# Main_v1.net
KiCad netlist of a schematic drawn in EAGLE
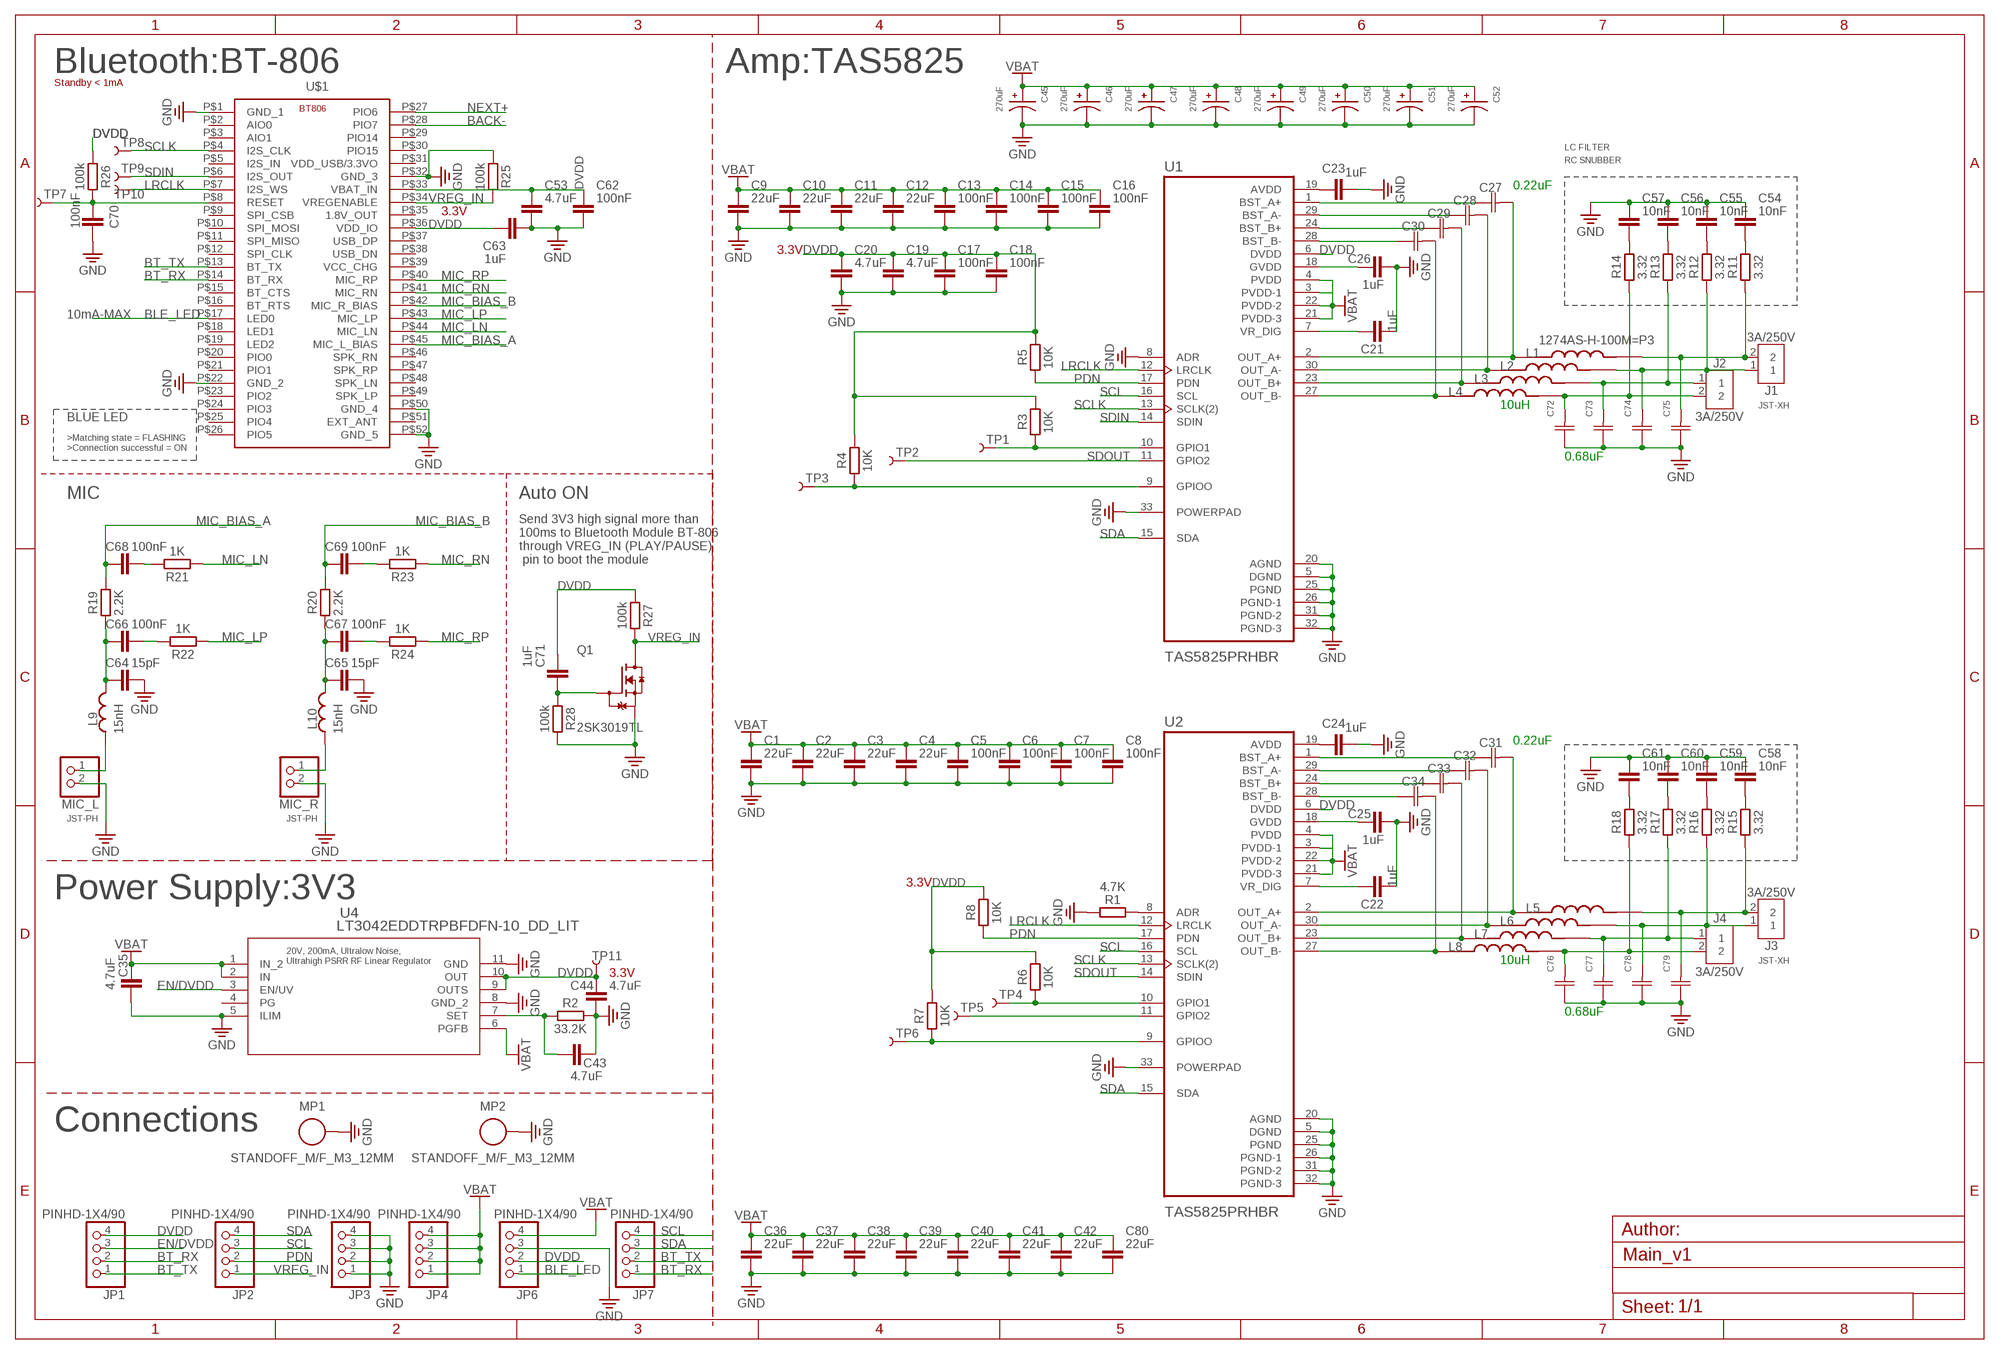
[diagram p0: schematic, sheet 1]

(export (version "E")
  (design (tool "Eeschema 10.0.6"))
  (components
    (comp (ref "C1")
      (value "22uF")
      (footprint "eagle-import:CAPC2012X110")
      (libsource (lib "eagle-import") (part "CCHIP-0805(2012-METRIC)_"))
    )
    (comp (ref "C2")
      (value "22uF")
      (footprint "eagle-import:CAPC2012X110")
      (libsource (lib "eagle-import") (part "CCHIP-0805(2012-METRIC)_"))
    )
    (comp (ref "C3")
      (value "22uF")
      (footprint "eagle-import:CAPC2012X110")
      (libsource (lib "eagle-import") (part "CCHIP-0805(2012-METRIC)_"))
    )
    (comp (ref "C4")
      (value "22uF")
      (footprint "eagle-import:CAPC2012X110")
      (libsource (lib "eagle-import") (part "CCHIP-0805(2012-METRIC)_"))
    )
    (comp (ref "C5")
      (value "100nF")
      (footprint "eagle-import:CAPC2012X110")
      (libsource (lib "eagle-import") (part "CCHIP-0805(2012-METRIC)_"))
    )
    (comp (ref "C6")
      (value "100nF")
      (footprint "eagle-import:CAPC2012X110")
      (libsource (lib "eagle-import") (part "CCHIP-0805(2012-METRIC)_"))
    )
    (comp (ref "C7")
      (value "100nF")
      (footprint "eagle-import:CAPC2012X110")
      (libsource (lib "eagle-import") (part "CCHIP-0805(2012-METRIC)_"))
    )
    (comp (ref "C8")
      (value "100nF")
      (footprint "eagle-import:CAPC2012X110")
      (libsource (lib "eagle-import") (part "CCHIP-0805(2012-METRIC)_"))
    )
    (comp (ref "C9")
      (value "22uF")
      (footprint "eagle-import:CAPC2012X110")
      (libsource (lib "eagle-import") (part "CCHIP-0805(2012-METRIC)_"))
    )
    (comp (ref "C10")
      (value "22uF")
      (footprint "eagle-import:CAPC2012X110")
      (libsource (lib "eagle-import") (part "CCHIP-0805(2012-METRIC)_"))
    )
    (comp (ref "C11")
      (value "22uF")
      (footprint "eagle-import:CAPC2012X110")
      (libsource (lib "eagle-import") (part "CCHIP-0805(2012-METRIC)_"))
    )
    (comp (ref "C12")
      (value "22uF")
      (footprint "eagle-import:CAPC2012X110")
      (libsource (lib "eagle-import") (part "CCHIP-0805(2012-METRIC)_"))
    )
    (comp (ref "C13")
      (value "100nF")
      (footprint "eagle-import:CAPC2012X110")
      (libsource (lib "eagle-import") (part "CCHIP-0805(2012-METRIC)_"))
    )
    (comp (ref "C14")
      (value "100nF")
      (footprint "eagle-import:CAPC2012X110")
      (libsource (lib "eagle-import") (part "CCHIP-0805(2012-METRIC)_"))
    )
    (comp (ref "C15")
      (value "100nF")
      (footprint "eagle-import:CAPC2012X110")
      (libsource (lib "eagle-import") (part "CCHIP-0805(2012-METRIC)_"))
    )
    (comp (ref "C16")
      (value "100nF")
      (footprint "eagle-import:CAPC2012X110")
      (libsource (lib "eagle-import") (part "CCHIP-0805(2012-METRIC)_"))
    )
    (comp (ref "C17")
      (value "100nF")
      (footprint "eagle-import:CAPC2012X110")
      (libsource (lib "eagle-import") (part "CCHIP-0805(2012-METRIC)_"))
    )
    (comp (ref "C18")
      (value "100nF")
      (footprint "eagle-import:CAPC2012X110")
      (libsource (lib "eagle-import") (part "CCHIP-0805(2012-METRIC)_"))
    )
    (comp (ref "C19")
      (value "4.7uF")
      (footprint "eagle-import:CAPC3216X135")
      (libsource (lib "eagle-import") (part "CCHIP-1206(3216-METRIC)_"))
    )
    (comp (ref "C20")
      (value "4.7uF")
      (footprint "eagle-import:CAPC3216X135")
      (libsource (lib "eagle-import") (part "CCHIP-1206(3216-METRIC)_"))
    )
    (comp (ref "C21")
      (value "1uF")
      (footprint "eagle-import:CAPC2012X110")
      (libsource (lib "eagle-import") (part "CCHIP-0805(2012-METRIC)_"))
    )
    (comp (ref "C22")
      (value "1uF")
      (footprint "eagle-import:CAPC2012X110")
      (libsource (lib "eagle-import") (part "CCHIP-0805(2012-METRIC)_"))
    )
    (comp (ref "C23")
      (value "1uF")
      (footprint "eagle-import:CAPC2012X110")
      (libsource (lib "eagle-import") (part "CCHIP-0805(2012-METRIC)_"))
    )
    (comp (ref "C24")
      (value "1uF")
      (footprint "eagle-import:CAPC2012X110")
      (libsource (lib "eagle-import") (part "CCHIP-0805(2012-METRIC)_"))
    )
    (comp (ref "C25")
      (value "1uF")
      (footprint "eagle-import:CAPC2012X110")
      (libsource (lib "eagle-import") (part "CCHIP-0805(2012-METRIC)_"))
    )
    (comp (ref "C26")
      (value "1uF")
      (footprint "eagle-import:CAPC2012X110")
      (libsource (lib "eagle-import") (part "CCHIP-0805(2012-METRIC)_"))
    )
    (comp (ref "C27")
      (value "0.22uF")
      (footprint "eagle-import:CAPM7.2X7.2_5_1_VIS")
      (fields
        (field (name "MANUFACTURER_PART_NUMBER") "PHE426HJ6220JR05")
        (field (name "COPYRIGHT") "Copyright (C) 2021 Ultra Librarian. All rights reserved.")
      )
      (libsource (lib "eagle-import") (part "PHE426HJ6220JR05CAPM7.2X7.2_5_1_VIS"))
    )
    (comp (ref "C28")
      (value "0.22uF")
      (footprint "eagle-import:CAPM7.2X7.2_5_1_VIS")
      (fields
        (field (name "MANUFACTURER_PART_NUMBER") "PHE426HJ6220JR05")
        (field (name "COPYRIGHT") "Copyright (C) 2021 Ultra Librarian. All rights reserved.")
      )
      (libsource (lib "eagle-import") (part "PHE426HJ6220JR05CAPM7.2X7.2_5_1_VIS"))
    )
    (comp (ref "C29")
      (value "0.22uF")
      (footprint "eagle-import:CAPM7.2X7.2_5_1_VIS")
      (fields
        (field (name "MANUFACTURER_PART_NUMBER") "PHE426HJ6220JR05")
        (field (name "COPYRIGHT") "Copyright (C) 2021 Ultra Librarian. All rights reserved.")
      )
      (libsource (lib "eagle-import") (part "PHE426HJ6220JR05CAPM7.2X7.2_5_1_VIS"))
    )
    (comp (ref "C30")
      (value "0.22uF")
      (footprint "eagle-import:CAPM7.2X7.2_5_1_VIS")
      (fields
        (field (name "MANUFACTURER_PART_NUMBER") "PHE426HJ6220JR05")
        (field (name "COPYRIGHT") "Copyright (C) 2021 Ultra Librarian. All rights reserved.")
      )
      (libsource (lib "eagle-import") (part "PHE426HJ6220JR05CAPM7.2X7.2_5_1_VIS"))
    )
    (comp (ref "C31")
      (value "0.22uF")
      (footprint "eagle-import:CAPM7.2X7.2_5_1_VIS")
      (fields
        (field (name "MANUFACTURER_PART_NUMBER") "PHE426HJ6220JR05")
        (field (name "COPYRIGHT") "Copyright (C) 2021 Ultra Librarian. All rights reserved.")
      )
      (libsource (lib "eagle-import") (part "PHE426HJ6220JR05CAPM7.2X7.2_5_1_VIS"))
    )
    (comp (ref "C32")
      (value "0.22uF")
      (footprint "eagle-import:CAPM7.2X7.2_5_1_VIS")
      (fields
        (field (name "MANUFACTURER_PART_NUMBER") "PHE426HJ6220JR05")
        (field (name "COPYRIGHT") "Copyright (C) 2021 Ultra Librarian. All rights reserved.")
      )
      (libsource (lib "eagle-import") (part "PHE426HJ6220JR05CAPM7.2X7.2_5_1_VIS"))
    )
    (comp (ref "C33")
      (value "0.22uF")
      (footprint "eagle-import:CAPM7.2X7.2_5_1_VIS")
      (fields
        (field (name "MANUFACTURER_PART_NUMBER") "PHE426HJ6220JR05")
        (field (name "COPYRIGHT") "Copyright (C) 2021 Ultra Librarian. All rights reserved.")
      )
      (libsource (lib "eagle-import") (part "PHE426HJ6220JR05CAPM7.2X7.2_5_1_VIS"))
    )
    (comp (ref "C34")
      (value "0.22uF")
      (footprint "eagle-import:CAPM7.2X7.2_5_1_VIS")
      (fields
        (field (name "MANUFACTURER_PART_NUMBER") "PHE426HJ6220JR05")
        (field (name "COPYRIGHT") "Copyright (C) 2021 Ultra Librarian. All rights reserved.")
      )
      (libsource (lib "eagle-import") (part "PHE426HJ6220JR05CAPM7.2X7.2_5_1_VIS"))
    )
    (comp (ref "C35")
      (value "4.7uF")
      (footprint "eagle-import:CAPC2012X110")
      (libsource (lib "eagle-import") (part "CCHIP-0805(2012-METRIC)_"))
    )
    (comp (ref "C36")
      (value "22uF")
      (footprint "eagle-import:CAPC2012X110")
      (libsource (lib "eagle-import") (part "CCHIP-0805(2012-METRIC)_"))
    )
    (comp (ref "C37")
      (value "22uF")
      (footprint "eagle-import:CAPC2012X110")
      (libsource (lib "eagle-import") (part "CCHIP-0805(2012-METRIC)_"))
    )
    (comp (ref "C38")
      (value "22uF")
      (footprint "eagle-import:CAPC2012X110")
      (libsource (lib "eagle-import") (part "CCHIP-0805(2012-METRIC)_"))
    )
    (comp (ref "C39")
      (value "22uF")
      (footprint "eagle-import:CAPC2012X110")
      (libsource (lib "eagle-import") (part "CCHIP-0805(2012-METRIC)_"))
    )
    (comp (ref "C40")
      (value "22uF")
      (footprint "eagle-import:CAPC2012X110")
      (libsource (lib "eagle-import") (part "CCHIP-0805(2012-METRIC)_"))
    )
    (comp (ref "C41")
      (value "22uF")
      (footprint "eagle-import:CAPC2012X110")
      (libsource (lib "eagle-import") (part "CCHIP-0805(2012-METRIC)_"))
    )
    (comp (ref "C42")
      (value "22uF")
      (footprint "eagle-import:CAPC2012X110")
      (libsource (lib "eagle-import") (part "CCHIP-0805(2012-METRIC)_"))
    )
    (comp (ref "C43")
      (value "4.7uF")
      (footprint "eagle-import:CAPC2012X110")
      (libsource (lib "eagle-import") (part "CCHIP-0805(2012-METRIC)_"))
    )
    (comp (ref "C44")
      (value "4.7uF")
      (footprint "eagle-import:CAPC2012X110")
      (libsource (lib "eagle-import") (part "CCHIP-0805(2012-METRIC)_"))
    )
    (comp (ref "C45")
      (value "270uF")
      (footprint "eagle-import:CAP_16SVPG270M")
      (fields (field (name "MANUFACTURER") "Panasonic"))
      (libsource (lib "eagle-import") (part "16SVPG270M"))
    )
    (comp (ref "C46")
      (value "270uF")
      (footprint "eagle-import:CAP_16SVPG270M")
      (fields (field (name "MANUFACTURER") "Panasonic"))
      (libsource (lib "eagle-import") (part "16SVPG270M"))
    )
    (comp (ref "C47")
      (value "270uF")
      (footprint "eagle-import:CAP_16SVPG270M")
      (fields (field (name "MANUFACTURER") "Panasonic"))
      (libsource (lib "eagle-import") (part "16SVPG270M"))
    )
    (comp (ref "C48")
      (value "270uF")
      (footprint "eagle-import:CAP_16SVPG270M")
      (fields (field (name "MANUFACTURER") "Panasonic"))
      (libsource (lib "eagle-import") (part "16SVPG270M"))
    )
    (comp (ref "C49")
      (value "270uF")
      (footprint "eagle-import:CAP_16SVPG270M")
      (fields (field (name "MANUFACTURER") "Panasonic"))
      (libsource (lib "eagle-import") (part "16SVPG270M"))
    )
    (comp (ref "C50")
      (value "270uF")
      (footprint "eagle-import:CAP_16SVPG270M")
      (fields (field (name "MANUFACTURER") "Panasonic"))
      (libsource (lib "eagle-import") (part "16SVPG270M"))
    )
    (comp (ref "C51")
      (value "270uF")
      (footprint "eagle-import:CAP_16SVPG270M")
      (fields (field (name "MANUFACTURER") "Panasonic"))
      (libsource (lib "eagle-import") (part "16SVPG270M"))
    )
    (comp (ref "C52")
      (value "270uF")
      (footprint "eagle-import:CAP_16SVPG270M")
      (fields (field (name "MANUFACTURER") "Panasonic"))
      (libsource (lib "eagle-import") (part "16SVPG270M"))
    )
    (comp (ref "C53")
      (value "4.7uF")
      (footprint "eagle-import:CAPC2012X110")
      (libsource (lib "eagle-import") (part "CCHIP-0805(2012-METRIC)_"))
    )
    (comp (ref "C54")
      (value "10nF")
      (footprint "eagle-import:CAPC2012X110")
      (libsource (lib "eagle-import") (part "CCHIP-0805(2012-METRIC)_"))
    )
    (comp (ref "C55")
      (value "10nF")
      (footprint "eagle-import:CAPC2012X110")
      (libsource (lib "eagle-import") (part "CCHIP-0805(2012-METRIC)_"))
    )
    (comp (ref "C56")
      (value "10nF")
      (footprint "eagle-import:CAPC2012X110")
      (libsource (lib "eagle-import") (part "CCHIP-0805(2012-METRIC)_"))
    )
    (comp (ref "C57")
      (value "10nF")
      (footprint "eagle-import:CAPC2012X110")
      (libsource (lib "eagle-import") (part "CCHIP-0805(2012-METRIC)_"))
    )
    (comp (ref "C58")
      (value "10nF")
      (footprint "eagle-import:CAPC2012X110")
      (libsource (lib "eagle-import") (part "CCHIP-0805(2012-METRIC)_"))
    )
    (comp (ref "C59")
      (value "10nF")
      (footprint "eagle-import:CAPC2012X110")
      (libsource (lib "eagle-import") (part "CCHIP-0805(2012-METRIC)_"))
    )
    (comp (ref "C60")
      (value "10nF")
      (footprint "eagle-import:CAPC2012X110")
      (libsource (lib "eagle-import") (part "CCHIP-0805(2012-METRIC)_"))
    )
    (comp (ref "C61")
      (value "10nF")
      (footprint "eagle-import:CAPC2012X110")
      (libsource (lib "eagle-import") (part "CCHIP-0805(2012-METRIC)_"))
    )
    (comp (ref "C62")
      (value "100nF")
      (footprint "eagle-import:CAPC2012X110")
      (libsource (lib "eagle-import") (part "CCHIP-0805(2012-METRIC)_"))
    )
    (comp (ref "C63")
      (value "1uF")
      (footprint "eagle-import:CAPC2012X110")
      (libsource (lib "eagle-import") (part "CCHIP-0805(2012-METRIC)_"))
    )
    (comp (ref "C64")
      (value "15pF")
      (footprint "eagle-import:CAPC1005X60")
      (libsource (lib "eagle-import") (part "CCHIP-0402(1005-METRIC)_"))
    )
    (comp (ref "C65")
      (value "15pF")
      (footprint "eagle-import:CAPC1005X60")
      (libsource (lib "eagle-import") (part "CCHIP-0402(1005-METRIC)_"))
    )
    (comp (ref "C66")
      (value "100nF")
      (footprint "eagle-import:CAPC1005X60")
      (libsource (lib "eagle-import") (part "CCHIP-0402(1005-METRIC)_"))
    )
    (comp (ref "C67")
      (value "100nF")
      (footprint "eagle-import:CAPC1005X60")
      (libsource (lib "eagle-import") (part "CCHIP-0402(1005-METRIC)_"))
    )
    (comp (ref "C68")
      (value "100nF")
      (footprint "eagle-import:CAPC1005X60")
      (libsource (lib "eagle-import") (part "CCHIP-0402(1005-METRIC)_"))
    )
    (comp (ref "C69")
      (value "100nF")
      (footprint "eagle-import:CAPC1005X60")
      (libsource (lib "eagle-import") (part "CCHIP-0402(1005-METRIC)_"))
    )
    (comp (ref "C70")
      (value "100nF")
      (footprint "eagle-import:CAPC1005X60")
      (libsource (lib "eagle-import") (part "CCHIP-0402(1005-METRIC)_"))
    )
    (comp (ref "C71")
      (value "1uF")
      (footprint "eagle-import:CAPC2012X110")
      (libsource (lib "eagle-import") (part "CCHIP-0805(2012-METRIC)_"))
    )
    (comp (ref "C72")
      (value "MMK5684J63J03L16.5TR18CAPM7.2X4.5_5_VIS")
      (footprint "eagle-import:CAPM7.2X4.5_5_VIS")
      (fields
        (field (name "MANUFACTURER_PART_NUMBER") "MMK5684J63J03L16.5TR18")
        (field (name "COPYRIGHT") "Copyright (C) 2022 Ultra Librarian. All rights reserved.")
      )
      (libsource (lib "eagle-import") (part "MMK5684J63J03L16.5TR18CAPM7.2X4.5_5_VIS"))
    )
    (comp (ref "C73")
      (value "MMK5684J63J03L16.5TR18CAPM7.2X4.5_5_VIS")
      (footprint "eagle-import:CAPM7.2X4.5_5_VIS")
      (fields
        (field (name "MANUFACTURER_PART_NUMBER") "MMK5684J63J03L16.5TR18")
        (field (name "COPYRIGHT") "Copyright (C) 2022 Ultra Librarian. All rights reserved.")
      )
      (libsource (lib "eagle-import") (part "MMK5684J63J03L16.5TR18CAPM7.2X4.5_5_VIS"))
    )
    (comp (ref "C74")
      (value "MMK5684J63J03L16.5TR18CAPM7.2X4.5_5_VIS")
      (footprint "eagle-import:CAPM7.2X4.5_5_VIS")
      (fields
        (field (name "MANUFACTURER_PART_NUMBER") "MMK5684J63J03L16.5TR18")
        (field (name "COPYRIGHT") "Copyright (C) 2022 Ultra Librarian. All rights reserved.")
      )
      (libsource (lib "eagle-import") (part "MMK5684J63J03L16.5TR18CAPM7.2X4.5_5_VIS"))
    )
    (comp (ref "C75")
      (value "MMK5684J63J03L16.5TR18CAPM7.2X4.5_5_VIS")
      (footprint "eagle-import:CAPM7.2X4.5_5_VIS")
      (fields
        (field (name "MANUFACTURER_PART_NUMBER") "MMK5684J63J03L16.5TR18")
        (field (name "COPYRIGHT") "Copyright (C) 2022 Ultra Librarian. All rights reserved.")
      )
      (libsource (lib "eagle-import") (part "MMK5684J63J03L16.5TR18CAPM7.2X4.5_5_VIS"))
    )
    (comp (ref "C76")
      (value "MMK5684J63J03L16.5TR18CAPM7.2X4.5_5_VIS")
      (footprint "eagle-import:CAPM7.2X4.5_5_VIS")
      (fields
        (field (name "MANUFACTURER_PART_NUMBER") "MMK5684J63J03L16.5TR18")
        (field (name "COPYRIGHT") "Copyright (C) 2022 Ultra Librarian. All rights reserved.")
      )
      (libsource (lib "eagle-import") (part "MMK5684J63J03L16.5TR18CAPM7.2X4.5_5_VIS"))
    )
    (comp (ref "C77")
      (value "MMK5684J63J03L16.5TR18CAPM7.2X4.5_5_VIS")
      (footprint "eagle-import:CAPM7.2X4.5_5_VIS")
      (fields
        (field (name "MANUFACTURER_PART_NUMBER") "MMK5684J63J03L16.5TR18")
        (field (name "COPYRIGHT") "Copyright (C) 2022 Ultra Librarian. All rights reserved.")
      )
      (libsource (lib "eagle-import") (part "MMK5684J63J03L16.5TR18CAPM7.2X4.5_5_VIS"))
    )
    (comp (ref "C78")
      (value "MMK5684J63J03L16.5TR18CAPM7.2X4.5_5_VIS")
      (footprint "eagle-import:CAPM7.2X4.5_5_VIS")
      (fields
        (field (name "MANUFACTURER_PART_NUMBER") "MMK5684J63J03L16.5TR18")
        (field (name "COPYRIGHT") "Copyright (C) 2022 Ultra Librarian. All rights reserved.")
      )
      (libsource (lib "eagle-import") (part "MMK5684J63J03L16.5TR18CAPM7.2X4.5_5_VIS"))
    )
    (comp (ref "C79")
      (value "MMK5684J63J03L16.5TR18CAPM7.2X4.5_5_VIS")
      (footprint "eagle-import:CAPM7.2X4.5_5_VIS")
      (fields
        (field (name "MANUFACTURER_PART_NUMBER") "MMK5684J63J03L16.5TR18")
        (field (name "COPYRIGHT") "Copyright (C) 2022 Ultra Librarian. All rights reserved.")
      )
      (libsource (lib "eagle-import") (part "MMK5684J63J03L16.5TR18CAPM7.2X4.5_5_VIS"))
    )
    (comp (ref "C80")
      (value "22uF")
      (footprint "eagle-import:CAPC2012X110")
      (libsource (lib "eagle-import") (part "CCHIP-0805(2012-METRIC)_"))
    )
    (comp (ref "J1")
      (value "3A/250V")
      (footprint "eagle-import:B2B-XH-A")
      (fields (field (name "MANUFACTURER") "JST (XH CONNECTOR)") (field (name "MPN") "B2B-XH-A"))
      (libsource (lib "eagle-import") (part "B2B-XH-A"))
    )
    (comp (ref "J2")
      (value "3A/250V")
      (footprint "eagle-import:B2B-XH-A")
      (fields (field (name "MANUFACTURER") "JST (XH CONNECTOR)") (field (name "MPN") "B2B-XH-A"))
      (libsource (lib "eagle-import") (part "B2B-XH-A"))
    )
    (comp (ref "J3")
      (value "3A/250V")
      (footprint "eagle-import:B2B-XH-A")
      (fields (field (name "MANUFACTURER") "JST (XH CONNECTOR)") (field (name "MPN") "B2B-XH-A"))
      (libsource (lib "eagle-import") (part "B2B-XH-A"))
    )
    (comp (ref "J4")
      (value "3A/250V")
      (footprint "eagle-import:B2B-XH-A")
      (fields (field (name "MANUFACTURER") "JST (XH CONNECTOR)") (field (name "MPN") "B2B-XH-A"))
      (libsource (lib "eagle-import") (part "B2B-XH-A"))
    )
    (comp (ref "JP1")
      (value "PINHD-1X4/90")
      (footprint "eagle-import:1X04_90")
      (libsource (lib "eagle-import") (part "PINHD-1X4/90"))
    )
    (comp (ref "JP2")
      (value "PINHD-1X4/90")
      (footprint "eagle-import:1X04_90")
      (libsource (lib "eagle-import") (part "PINHD-1X4/90"))
    )
    (comp (ref "JP3")
      (value "PINHD-1X4/90")
      (footprint "eagle-import:1X04_90")
      (libsource (lib "eagle-import") (part "PINHD-1X4/90"))
    )
    (comp (ref "JP4")
      (value "PINHD-1X4/90")
      (footprint "eagle-import:1X04_90")
      (libsource (lib "eagle-import") (part "PINHD-1X4/90"))
    )
    (comp (ref "JP6")
      (value "PINHD-1X4/90")
      (footprint "eagle-import:1X04_90")
      (libsource (lib "eagle-import") (part "PINHD-1X4/90"))
    )
    (comp (ref "JP7")
      (value "PINHD-1X4/90")
      (footprint "eagle-import:1X04_90")
      (libsource (lib "eagle-import") (part "PINHD-1X4/90"))
    )
    (comp (ref "L1")
      (value "1274AS-H-100M=P3")
      (footprint "eagle-import:IND_1274AS-H-100M=P3")
      (fields (field (name "MANUFACTURER") "Murata"))
      (libsource (lib "eagle-import") (part "1274AS-H-100M=P3"))
    )
    (comp (ref "L2")
      (value "1274AS-H-100M=P3")
      (footprint "eagle-import:IND_1274AS-H-100M=P3")
      (fields (field (name "MANUFACTURER") "Murata"))
      (libsource (lib "eagle-import") (part "1274AS-H-100M=P3"))
    )
    (comp (ref "L3")
      (value "1274AS-H-100M=P3")
      (footprint "eagle-import:IND_1274AS-H-100M=P3")
      (fields (field (name "MANUFACTURER") "Murata"))
      (libsource (lib "eagle-import") (part "1274AS-H-100M=P3"))
    )
    (comp (ref "L4")
      (value "1274AS-H-100M=P3")
      (footprint "eagle-import:IND_1274AS-H-100M=P3")
      (fields (field (name "MANUFACTURER") "Murata"))
      (libsource (lib "eagle-import") (part "1274AS-H-100M=P3"))
    )
    (comp (ref "L5")
      (value "1274AS-H-100M=P3")
      (footprint "eagle-import:IND_1274AS-H-100M=P3")
      (fields (field (name "MANUFACTURER") "Murata"))
      (libsource (lib "eagle-import") (part "1274AS-H-100M=P3"))
    )
    (comp (ref "L6")
      (value "1274AS-H-100M=P3")
      (footprint "eagle-import:IND_1274AS-H-100M=P3")
      (fields (field (name "MANUFACTURER") "Murata"))
      (libsource (lib "eagle-import") (part "1274AS-H-100M=P3"))
    )
    (comp (ref "L7")
      (value "1274AS-H-100M=P3")
      (footprint "eagle-import:IND_1274AS-H-100M=P3")
      (fields (field (name "MANUFACTURER") "Murata"))
      (libsource (lib "eagle-import") (part "1274AS-H-100M=P3"))
    )
    (comp (ref "L8")
      (value "1274AS-H-100M=P3")
      (footprint "eagle-import:IND_1274AS-H-100M=P3")
      (fields (field (name "MANUFACTURER") "Murata"))
      (libsource (lib "eagle-import") (part "1274AS-H-100M=P3"))
    )
    (comp (ref "L9")
      (value "15nH")
      (footprint "eagle-import:INDC1006X60N")
      (libsource (lib "eagle-import") (part "LCHIP-0402(1006-METRIC)_"))
    )
    (comp (ref "L10")
      (value "15nH")
      (footprint "eagle-import:INDC1006X60N")
      (libsource (lib "eagle-import") (part "LCHIP-0402(1006-METRIC)_"))
    )
    (comp (ref "MIC_L")
      (value "JST_2PIN-THM")
      (footprint "eagle-import:JST-PH-2-THM")
      (libsource (lib "eagle-import") (part "JST_2PIN-THM"))
    )
    (comp (ref "MIC_R")
      (value "JST_2PIN-THM")
      (footprint "eagle-import:JST-PH-2-THM")
      (libsource (lib "eagle-import") (part "JST_2PIN-THM"))
    )
    (comp (ref "MP1")
      (value "STANDOFF_M/F_M3_12MM")
      (footprint "eagle-import:STANDOFF_HEX_MALE-FEMALE_550X1200_M3X0.5_MTGP850H320")
      (libsource (lib "eagle-import") (part "STANDOFF_M/FM3_12MM_"))
    )
    (comp (ref "MP2")
      (value "STANDOFF_M/F_M3_12MM")
      (footprint "eagle-import:STANDOFF_HEX_MALE-FEMALE_550X1200_M3X0.5_MTGP850H320")
      (libsource (lib "eagle-import") (part "STANDOFF_M/FM3_12MM_"))
    )
    (comp (ref "Q1")
      (value "2SK3019TL")
      (footprint "eagle-import:TRANS_2SK3019TL")
      (fields (field (name "MANUFACTURER") "ROHM"))
      (libsource (lib "eagle-import") (part "2SK3019TL"))
    )
    (comp (ref "R1")
      (value "4.7K")
      (footprint "eagle-import:RESC1005X40")
      (libsource (lib "eagle-import") (part "RCHIP-0402(1005-METRIC)_"))
    )
    (comp (ref "R2")
      (value "33.2K")
      (footprint "eagle-import:RESC1005X40")
      (libsource (lib "eagle-import") (part "RCHIP-0402(1005-METRIC)_"))
    )
    (comp (ref "R3")
      (value "10K")
      (footprint "eagle-import:RESC1005X40")
      (libsource (lib "eagle-import") (part "RCHIP-0402(1005-METRIC)_"))
    )
    (comp (ref "R4")
      (value "10K")
      (footprint "eagle-import:RESC1005X40")
      (libsource (lib "eagle-import") (part "RCHIP-0402(1005-METRIC)_"))
    )
    (comp (ref "R5")
      (value "10K")
      (footprint "eagle-import:RESC1005X40")
      (libsource (lib "eagle-import") (part "RCHIP-0402(1005-METRIC)_"))
    )
    (comp (ref "R6")
      (value "10K")
      (footprint "eagle-import:RESC1005X40")
      (libsource (lib "eagle-import") (part "RCHIP-0402(1005-METRIC)_"))
    )
    (comp (ref "R7")
      (value "10K")
      (footprint "eagle-import:RESC1005X40")
      (libsource (lib "eagle-import") (part "RCHIP-0402(1005-METRIC)_"))
    )
    (comp (ref "R8")
      (value "10K")
      (footprint "eagle-import:RESC1005X40")
      (libsource (lib "eagle-import") (part "RCHIP-0402(1005-METRIC)_"))
    )
    (comp (ref "R11")
      (value "3.32")
      (footprint "eagle-import:RESC1005X40")
      (libsource (lib "eagle-import") (part "RCHIP-0402(1005-METRIC)_"))
    )
    (comp (ref "R12")
      (value "3.32")
      (footprint "eagle-import:RESC1005X40")
      (libsource (lib "eagle-import") (part "RCHIP-0402(1005-METRIC)_"))
    )
    (comp (ref "R13")
      (value "3.32")
      (footprint "eagle-import:RESC1005X40")
      (libsource (lib "eagle-import") (part "RCHIP-0402(1005-METRIC)_"))
    )
    (comp (ref "R14")
      (value "3.32")
      (footprint "eagle-import:RESC1005X40")
      (libsource (lib "eagle-import") (part "RCHIP-0402(1005-METRIC)_"))
    )
    (comp (ref "R15")
      (value "3.32")
      (footprint "eagle-import:RESC1005X40")
      (libsource (lib "eagle-import") (part "RCHIP-0402(1005-METRIC)_"))
    )
    (comp (ref "R16")
      (value "3.32")
      (footprint "eagle-import:RESC1005X40")
      (libsource (lib "eagle-import") (part "RCHIP-0402(1005-METRIC)_"))
    )
    (comp (ref "R17")
      (value "3.32")
      (footprint "eagle-import:RESC1005X40")
      (libsource (lib "eagle-import") (part "RCHIP-0402(1005-METRIC)_"))
    )
    (comp (ref "R18")
      (value "3.32")
      (footprint "eagle-import:RESC1005X40")
      (libsource (lib "eagle-import") (part "RCHIP-0402(1005-METRIC)_"))
    )
    (comp (ref "R19")
      (value "2.2K")
      (footprint "eagle-import:RESC1005X40")
      (libsource (lib "eagle-import") (part "RCHIP-0402(1005-METRIC)_"))
    )
    (comp (ref "R20")
      (value "2.2K")
      (footprint "eagle-import:RESC1005X40")
      (libsource (lib "eagle-import") (part "RCHIP-0402(1005-METRIC)_"))
    )
    (comp (ref "R21")
      (value "1K")
      (footprint "eagle-import:RESC1005X40")
      (libsource (lib "eagle-import") (part "RCHIP-0402(1005-METRIC)_"))
    )
    (comp (ref "R22")
      (value "1K")
      (footprint "eagle-import:RESC1005X40")
      (libsource (lib "eagle-import") (part "RCHIP-0402(1005-METRIC)_"))
    )
    (comp (ref "R23")
      (value "1K")
      (footprint "eagle-import:RESC1005X40")
      (libsource (lib "eagle-import") (part "RCHIP-0402(1005-METRIC)_"))
    )
    (comp (ref "R24")
      (value "1K")
      (footprint "eagle-import:RESC1005X40")
      (libsource (lib "eagle-import") (part "RCHIP-0402(1005-METRIC)_"))
    )
    (comp (ref "R25")
      (value "100k")
      (footprint "eagle-import:RESC1005X40")
      (libsource (lib "eagle-import") (part "RCHIP-0402(1005-METRIC)_"))
    )
    (comp (ref "R26")
      (value "100k")
      (footprint "eagle-import:RESC1005X40")
      (libsource (lib "eagle-import") (part "RCHIP-0402(1005-METRIC)_"))
    )
    (comp (ref "R27")
      (value "100k")
      (footprint "eagle-import:RESC1005X40")
      (libsource (lib "eagle-import") (part "RCHIP-0402(1005-METRIC)_"))
    )
    (comp (ref "R28")
      (value "100k")
      (footprint "eagle-import:RESC1005X40")
      (libsource (lib "eagle-import") (part "RCHIP-0402(1005-METRIC)_"))
    )
    (comp (ref "TP1")
      (value "TEST-POINT3")
      (footprint "eagle-import:PAD.03X.03")
      (libsource (lib "eagle-import") (part "TEST-POINT3"))
    )
    (comp (ref "TP2")
      (value "TEST-POINT3")
      (footprint "eagle-import:PAD.03X.03")
      (libsource (lib "eagle-import") (part "TEST-POINT3"))
    )
    (comp (ref "TP3")
      (value "TEST-POINT3")
      (footprint "eagle-import:PAD.03X.03")
      (libsource (lib "eagle-import") (part "TEST-POINT3"))
    )
    (comp (ref "TP4")
      (value "TEST-POINT3")
      (footprint "eagle-import:PAD.03X.03")
      (libsource (lib "eagle-import") (part "TEST-POINT3"))
    )
    (comp (ref "TP5")
      (value "TEST-POINT3")
      (footprint "eagle-import:PAD.03X.03")
      (libsource (lib "eagle-import") (part "TEST-POINT3"))
    )
    (comp (ref "TP6")
      (value "TEST-POINT3")
      (footprint "eagle-import:PAD.03X.03")
      (libsource (lib "eagle-import") (part "TEST-POINT3"))
    )
    (comp (ref "TP7")
      (value "TEST-POINT3")
      (footprint "eagle-import:PAD.03X.03")
      (libsource (lib "eagle-import") (part "TEST-POINT3"))
    )
    (comp (ref "TP8")
      (value "TEST-POINT3X5")
      (footprint "eagle-import:PAD.03X.05")
      (libsource (lib "eagle-import") (part "TEST-POINT3X5"))
    )
    (comp (ref "TP9")
      (value "TEST-POINT3X5")
      (footprint "eagle-import:PAD.03X.05")
      (libsource (lib "eagle-import") (part "TEST-POINT3X5"))
    )
    (comp (ref "TP10")
      (value "TEST-POINT3X5")
      (footprint "eagle-import:PAD.03X.05")
      (libsource (lib "eagle-import") (part "TEST-POINT3X5"))
    )
    (comp (ref "TP11")
      (value "TEST-POINT3X5")
      (footprint "eagle-import:PAD.03X.05")
      (libsource (lib "eagle-import") (part "TEST-POINT3X5"))
    )
    (comp (ref "U$1")
      (value "BT806")
      (footprint "eagle-import:BT806")
      (libsource (lib "eagle-import") (part "BT806"))
    )
    (comp (ref "U1")
      (value "TAS5825PRHBR")
      (footprint "eagle-import:IC_ADS125H01IRHBT")
      (libsource (lib "eagle-import") (part "TAS5825PRHBR"))
    )
    (comp (ref "U2")
      (value "TAS5825PRHBR")
      (footprint "eagle-import:IC_ADS125H01IRHBT")
      (libsource (lib "eagle-import") (part "TAS5825PRHBR"))
    )
    (comp (ref "U4")
      (value "LT3042EDDTRPBFDFN-10_DD_LIT")
      (footprint "eagle-import:DFN-10_DD_LIT")
      (fields
        (field (name "MANUFACTURER_PART_NUMBER") "LT3042EDD#TRPBF")
        (field (name "COPYRIGHT") "Copyright (C) 2021 Ultra Librarian. All rights reserved.")
      )
      (libsource (lib "eagle-import") (part "LT3042EDDTRPBFDFN-10_DD_LIT"))
    )
  )
  (nets
    (net (code "1") (name "/BACK-") (class "Default")
      (node (ref "U$1") (pin "P$28") (pinfunction "PIO7_P$28") (pintype "bidirectional"))
    )
    (net (code "2") (name "/BLE_LED") (class "Default")
      (node (ref "JP6") (pin "1") (pinfunction "1_1") (pintype "passive"))
      (node (ref "U$1") (pin "P$17") (pinfunction "LED0_P$17") (pintype "bidirectional"))
    )
    (net (code "3") (name "/BT_RX") (class "Default")
      (node (ref "JP1") (pin "2") (pinfunction "2_2") (pintype "passive"))
      (node (ref "JP7") (pin "1") (pinfunction "1_1") (pintype "passive"))
      (node (ref "U$1") (pin "P$14") (pinfunction "BT_RX_P$14") (pintype "bidirectional"))
    )
    (net (code "4") (name "/BT_TX") (class "Default")
      (node (ref "JP1") (pin "1") (pinfunction "1_1") (pintype "passive"))
      (node (ref "JP7") (pin "2") (pinfunction "2_2") (pintype "passive"))
      (node (ref "U$1") (pin "P$13") (pinfunction "BT_TX_P$13") (pintype "bidirectional"))
    )
    (net (code "5") (name "/DVDD") (class "Default")
      (node (ref "C17") (pin "1") (pinfunction "1_1") (pintype "passive"))
      (node (ref "C18") (pin "1") (pinfunction "1_1") (pintype "passive"))
      (node (ref "C19") (pin "1") (pinfunction "1_1") (pintype "passive"))
      (node (ref "C20") (pin "1") (pinfunction "1_1") (pintype "passive"))
      (node (ref "C44") (pin "2") (pinfunction "2_2") (pintype "passive"))
      (node (ref "C53") (pin "1") (pinfunction "1_1") (pintype "passive"))
      (node (ref "C62") (pin "1") (pinfunction "1_1") (pintype "passive"))
      (node (ref "C63") (pin "1") (pinfunction "1_1") (pintype "passive"))
      (node (ref "C71") (pin "1") (pinfunction "1_1") (pintype "passive"))
      (node (ref "JP1") (pin "4") (pinfunction "4_4") (pintype "passive"))
      (node (ref "JP6") (pin "2") (pinfunction "2_2") (pintype "passive"))
      (node (ref "R26") (pin "1") (pinfunction "1_1") (pintype "passive"))
      (node (ref "R27") (pin "1") (pinfunction "1_1") (pintype "passive"))
      (node (ref "R3") (pin "2") (pinfunction "2_2") (pintype "passive"))
      (node (ref "R4") (pin "2") (pinfunction "2_2") (pintype "passive"))
      (node (ref "R5") (pin "2") (pinfunction "2_2") (pintype "passive"))
      (node (ref "R6") (pin "2") (pinfunction "2_2") (pintype "passive"))
      (node (ref "R7") (pin "2") (pinfunction "2_2") (pintype "passive"))
      (node (ref "R8") (pin "2") (pinfunction "2_2") (pintype "passive"))
      (node (ref "TP11") (pin "P$1") (pinfunction "1_P$1") (pintype "bidirectional"))
      (node (ref "U$1") (pin "P$33") (pinfunction "VBAT_IN_P$33") (pintype "bidirectional"))
      (node (ref "U$1") (pin "P$36") (pinfunction "VDD_IO_P$36") (pintype "bidirectional"))
      (node (ref "U1") (pin "6") (pinfunction "DVDD_6") (pintype "power_in"))
      (node (ref "U2") (pin "6") (pinfunction "DVDD_6") (pintype "power_in"))
      (node (ref "U4") (pin "10") (pinfunction "OUT_10") (pintype "output"))
      (node (ref "U4") (pin "9") (pinfunction "OUTS_9") (pintype "output"))
    )
    (net (code "6") (name "/EN{slash}DVDD") (class "Default")
      (node (ref "JP1") (pin "3") (pinfunction "3_3") (pintype "passive"))
      (node (ref "U4") (pin "3") (pinfunction "EN/UV_3") (pintype "output"))
    )
    (net (code "7") (name "/LRCLK") (class "Default")
      (node (ref "TP10") (pin "P$1") (pinfunction "1_P$1") (pintype "bidirectional"))
      (node (ref "U$1") (pin "P$7") (pinfunction "I2S_WS_P$7") (pintype "bidirectional"))
      (node (ref "U1") (pin "12") (pinfunction "LRCLK_12") (pintype "input"))
      (node (ref "U2") (pin "12") (pinfunction "LRCLK_12") (pintype "input"))
    )
    (net (code "8") (name "/MIC_BIAS_A") (class "Default")
      (node (ref "C68") (pin "1") (pinfunction "1_1") (pintype "passive"))
      (node (ref "R19") (pin "2") (pinfunction "2_2") (pintype "passive"))
      (node (ref "U$1") (pin "P$45") (pinfunction "MIC_L_BIAS_P$45") (pintype "bidirectional"))
    )
    (net (code "9") (name "/MIC_BIAS_B") (class "Default")
      (node (ref "C69") (pin "1") (pinfunction "1_1") (pintype "passive"))
      (node (ref "R20") (pin "2") (pinfunction "2_2") (pintype "passive"))
      (node (ref "U$1") (pin "P$42") (pinfunction "MIC_R_BIAS_P$42") (pintype "bidirectional"))
    )
    (net (code "10") (name "/MIC_LN") (class "Default")
      (node (ref "R21") (pin "1") (pinfunction "1_1") (pintype "passive"))
      (node (ref "U$1") (pin "P$44") (pinfunction "MIC_LN_P$44") (pintype "bidirectional"))
    )
    (net (code "11") (name "/MIC_LP") (class "Default")
      (node (ref "R22") (pin "1") (pinfunction "1_1") (pintype "passive"))
      (node (ref "U$1") (pin "P$43") (pinfunction "MIC_LP_P$43") (pintype "bidirectional"))
    )
    (net (code "12") (name "/MIC_RN") (class "Default")
      (node (ref "R23") (pin "1") (pinfunction "1_1") (pintype "passive"))
      (node (ref "U$1") (pin "P$41") (pinfunction "MIC_RN_P$41") (pintype "bidirectional"))
    )
    (net (code "13") (name "/MIC_RP") (class "Default")
      (node (ref "R24") (pin "1") (pinfunction "1_1") (pintype "passive"))
      (node (ref "U$1") (pin "P$40") (pinfunction "MIC_RP_P$40") (pintype "bidirectional"))
    )
    (net (code "14") (name "/NEXT+") (class "Default")
      (node (ref "U$1") (pin "P$27") (pinfunction "PIO6_P$27") (pintype "bidirectional"))
    )
    (net (code "15") (name "/PDN") (class "Default")
      (node (ref "JP2") (pin "2") (pinfunction "2_2") (pintype "passive"))
      (node (ref "R5") (pin "1") (pinfunction "1_1") (pintype "passive"))
      (node (ref "R8") (pin "1") (pinfunction "1_1") (pintype "passive"))
      (node (ref "U1") (pin "17") (pinfunction "PDN_17") (pintype "input"))
      (node (ref "U2") (pin "17") (pinfunction "PDN_17") (pintype "input"))
    )
    (net (code "16") (name "/PG") (class "Default")
      (node (ref "U4") (pin "4") (pinfunction "PG_4") (pintype "power_in"))
    )
    (net (code "17") (name "/SCL") (class "Default")
      (node (ref "JP2") (pin "3") (pinfunction "3_3") (pintype "passive"))
      (node (ref "JP7") (pin "4") (pinfunction "4_4") (pintype "passive"))
      (node (ref "U1") (pin "16") (pinfunction "SCL_16") (pintype "input"))
      (node (ref "U2") (pin "16") (pinfunction "SCL_16") (pintype "input"))
    )
    (net (code "18") (name "/SCLK") (class "Default")
      (node (ref "TP8") (pin "P$1") (pinfunction "1_P$1") (pintype "bidirectional"))
      (node (ref "U$1") (pin "P$4") (pinfunction "I2S_CLK_P$4") (pintype "bidirectional"))
      (node (ref "U1") (pin "13") (pinfunction "SCLK(2)_13") (pintype "input"))
      (node (ref "U2") (pin "13") (pinfunction "SCLK(2)_13") (pintype "input"))
    )
    (net (code "19") (name "/SDA") (class "Default")
      (node (ref "JP2") (pin "4") (pinfunction "4_4") (pintype "passive"))
      (node (ref "JP7") (pin "3") (pinfunction "3_3") (pintype "passive"))
      (node (ref "U1") (pin "15") (pinfunction "SDA_15") (pintype "bidirectional"))
      (node (ref "U2") (pin "15") (pinfunction "SDA_15") (pintype "bidirectional"))
    )
    (net (code "20") (name "/SDIN") (class "Default")
      (node (ref "TP9") (pin "P$1") (pinfunction "1_P$1") (pintype "bidirectional"))
      (node (ref "U$1") (pin "P$6") (pinfunction "I2S_OUT_P$6") (pintype "bidirectional"))
      (node (ref "U1") (pin "14") (pinfunction "SDIN_14") (pintype "input"))
    )
    (net (code "21") (name "/SDOUT") (class "Default")
      (node (ref "TP2") (pin "P$1") (pinfunction "1_P$1") (pintype "bidirectional"))
      (node (ref "U1") (pin "11") (pinfunction "GPIO2_11") (pintype "bidirectional"))
      (node (ref "U2") (pin "14") (pinfunction "SDIN_14") (pintype "input"))
    )
    (net (code "22") (name "/VREG_IN") (class "Default")
      (node (ref "JP2") (pin "1") (pinfunction "1_1") (pintype "passive"))
      (node (ref "Q1") (pin "3") (pinfunction "D_3") (pintype "passive"))
      (node (ref "R25") (pin "2") (pinfunction "2_2") (pintype "passive"))
      (node (ref "R27") (pin "2") (pinfunction "2_2") (pintype "passive"))
      (node (ref "U$1") (pin "P$34") (pinfunction "VREGENABLE_P$34") (pintype "bidirectional"))
    )
    (net (code "23") (name "GND") (class "Default")
      (node (ref "C1") (pin "2") (pinfunction "2_2") (pintype "passive"))
      (node (ref "C10") (pin "2") (pinfunction "2_2") (pintype "passive"))
      (node (ref "C11") (pin "2") (pinfunction "2_2") (pintype "passive"))
      (node (ref "C12") (pin "2") (pinfunction "2_2") (pintype "passive"))
      (node (ref "C13") (pin "2") (pinfunction "2_2") (pintype "passive"))
      (node (ref "C14") (pin "2") (pinfunction "2_2") (pintype "passive"))
      (node (ref "C15") (pin "2") (pinfunction "2_2") (pintype "passive"))
      (node (ref "C16") (pin "2") (pinfunction "2_2") (pintype "passive"))
      (node (ref "C17") (pin "2") (pinfunction "2_2") (pintype "passive"))
      (node (ref "C18") (pin "2") (pinfunction "2_2") (pintype "passive"))
      (node (ref "C19") (pin "2") (pinfunction "2_2") (pintype "passive"))
      (node (ref "C2") (pin "2") (pinfunction "2_2") (pintype "passive"))
      (node (ref "C20") (pin "2") (pinfunction "2_2") (pintype "passive"))
      (node (ref "C21") (pin "2") (pinfunction "2_2") (pintype "passive"))
      (node (ref "C22") (pin "2") (pinfunction "2_2") (pintype "passive"))
      (node (ref "C23") (pin "2") (pinfunction "2_2") (pintype "passive"))
      (node (ref "C24") (pin "2") (pinfunction "2_2") (pintype "passive"))
      (node (ref "C25") (pin "2") (pinfunction "2_2") (pintype "passive"))
      (node (ref "C26") (pin "2") (pinfunction "2_2") (pintype "passive"))
      (node (ref "C3") (pin "2") (pinfunction "2_2") (pintype "passive"))
      (node (ref "C35") (pin "1") (pinfunction "1_1") (pintype "passive"))
      (node (ref "C36") (pin "2") (pinfunction "2_2") (pintype "passive"))
      (node (ref "C37") (pin "2") (pinfunction "2_2") (pintype "passive"))
      (node (ref "C38") (pin "2") (pinfunction "2_2") (pintype "passive"))
      (node (ref "C39") (pin "2") (pinfunction "2_2") (pintype "passive"))
      (node (ref "C4") (pin "2") (pinfunction "2_2") (pintype "passive"))
      (node (ref "C40") (pin "2") (pinfunction "2_2") (pintype "passive"))
      (node (ref "C41") (pin "2") (pinfunction "2_2") (pintype "passive"))
      (node (ref "C42") (pin "2") (pinfunction "2_2") (pintype "passive"))
      (node (ref "C43") (pin "2") (pinfunction "2_2") (pintype "passive"))
      (node (ref "C44") (pin "1") (pinfunction "1_1") (pintype "passive"))
      (node (ref "C45") (pin "2") (pinfunction "2_2") (pintype "passive"))
      (node (ref "C46") (pin "2") (pinfunction "2_2") (pintype "passive"))
      (node (ref "C47") (pin "2") (pinfunction "2_2") (pintype "passive"))
      (node (ref "C48") (pin "2") (pinfunction "2_2") (pintype "passive"))
      (node (ref "C49") (pin "2") (pinfunction "2_2") (pintype "passive"))
      (node (ref "C5") (pin "2") (pinfunction "2_2") (pintype "passive"))
      (node (ref "C50") (pin "2") (pinfunction "2_2") (pintype "passive"))
      (node (ref "C51") (pin "2") (pinfunction "2_2") (pintype "passive"))
      (node (ref "C52") (pin "2") (pinfunction "2_2") (pintype "passive"))
      (node (ref "C53") (pin "2") (pinfunction "2_2") (pintype "passive"))
      (node (ref "C54") (pin "1") (pinfunction "1_1") (pintype "passive"))
      (node (ref "C55") (pin "1") (pinfunction "1_1") (pintype "passive"))
      (node (ref "C56") (pin "1") (pinfunction "1_1") (pintype "passive"))
      (node (ref "C57") (pin "1") (pinfunction "1_1") (pintype "passive"))
      (node (ref "C58") (pin "1") (pinfunction "1_1") (pintype "passive"))
      (node (ref "C59") (pin "1") (pinfunction "1_1") (pintype "passive"))
      (node (ref "C6") (pin "2") (pinfunction "2_2") (pintype "passive"))
      (node (ref "C60") (pin "1") (pinfunction "1_1") (pintype "passive"))
      (node (ref "C61") (pin "1") (pinfunction "1_1") (pintype "passive"))
      (node (ref "C62") (pin "2") (pinfunction "2_2") (pintype "passive"))
      (node (ref "C63") (pin "2") (pinfunction "2_2") (pintype "passive"))
      (node (ref "C64") (pin "2") (pinfunction "2_2") (pintype "passive"))
      (node (ref "C65") (pin "2") (pinfunction "2_2") (pintype "passive"))
      (node (ref "C7") (pin "2") (pinfunction "2_2") (pintype "passive"))
      (node (ref "C70") (pin "1") (pinfunction "1_1") (pintype "passive"))
      (node (ref "C72") (pin "1") (pinfunction "1_1") (pintype "passive"))
      (node (ref "C73") (pin "1") (pinfunction "1_1") (pintype "passive"))
      (node (ref "C74") (pin "1") (pinfunction "1_1") (pintype "passive"))
      (node (ref "C75") (pin "1") (pinfunction "1_1") (pintype "passive"))
      (node (ref "C76") (pin "1") (pinfunction "1_1") (pintype "passive"))
      (node (ref "C77") (pin "1") (pinfunction "1_1") (pintype "passive"))
      (node (ref "C78") (pin "1") (pinfunction "1_1") (pintype "passive"))
      (node (ref "C79") (pin "1") (pinfunction "1_1") (pintype "passive"))
      (node (ref "C8") (pin "2") (pinfunction "2_2") (pintype "passive"))
      (node (ref "C80") (pin "2") (pinfunction "2_2") (pintype "passive"))
      (node (ref "C9") (pin "2") (pinfunction "2_2") (pintype "passive"))
      (node (ref "JP3") (pin "1") (pinfunction "1_1") (pintype "passive"))
      (node (ref "JP3") (pin "2") (pinfunction "2_2") (pintype "passive"))
      (node (ref "JP3") (pin "3") (pinfunction "3_3") (pintype "passive"))
      (node (ref "JP3") (pin "4") (pinfunction "4_4") (pintype "passive"))
      (node (ref "JP6") (pin "3") (pinfunction "3_3") (pintype "passive"))
      (node (ref "MIC_L") (pin "2") (pinfunction "1_2") (pintype "passive"))
      (node (ref "MIC_R") (pin "2") (pinfunction "1_2") (pintype "passive"))
      (node (ref "MP1") (pin "1") (pinfunction "P$1_1") (pintype "passive"))
      (node (ref "MP2") (pin "1") (pinfunction "P$1_1") (pintype "passive"))
      (node (ref "Q1") (pin "1") (pinfunction "S_1") (pintype "passive"))
      (node (ref "R1") (pin "1") (pinfunction "1_1") (pintype "passive"))
      (node (ref "R2") (pin "2") (pinfunction "2_2") (pintype "passive"))
      (node (ref "R25") (pin "1") (pinfunction "1_1") (pintype "passive"))
      (node (ref "R28") (pin "2") (pinfunction "2_2") (pintype "passive"))
      (node (ref "U$1") (pin "P$1") (pinfunction "GND_1_P$1") (pintype "bidirectional"))
      (node (ref "U$1") (pin "P$22") (pinfunction "GND_2_P$22") (pintype "bidirectional"))
      (node (ref "U$1") (pin "P$32") (pinfunction "GND_3_P$32") (pintype "bidirectional"))
      (node (ref "U$1") (pin "P$50") (pinfunction "GND_4_P$50") (pintype "bidirectional"))
      (node (ref "U$1") (pin "P$52") (pinfunction "GND_5_P$52") (pintype "bidirectional"))
      (node (ref "U1") (pin "20") (pinfunction "AGND_20") (pintype "power_in"))
      (node (ref "U1") (pin "25") (pinfunction "PGND_25") (pintype "power_in"))
      (node (ref "U1") (pin "26") (pinfunction "PGND-1_26") (pintype "power_in"))
      (node (ref "U1") (pin "31") (pinfunction "PGND-2_31") (pintype "power_in"))
      (node (ref "U1") (pin "32") (pinfunction "PGND-3_32") (pintype "power_in"))
      (node (ref "U1") (pin "33") (pinfunction "POWERPAD_33") (pintype "bidirectional"))
      (node (ref "U1") (pin "5") (pinfunction "DGND_5") (pintype "power_in"))
      (node (ref "U1") (pin "8") (pinfunction "ADR_8") (pintype "input"))
      (node (ref "U2") (pin "20") (pinfunction "AGND_20") (pintype "power_in"))
      (node (ref "U2") (pin "25") (pinfunction "PGND_25") (pintype "power_in"))
      (node (ref "U2") (pin "26") (pinfunction "PGND-1_26") (pintype "power_in"))
      (node (ref "U2") (pin "31") (pinfunction "PGND-2_31") (pintype "power_in"))
      (node (ref "U2") (pin "32") (pinfunction "PGND-3_32") (pintype "power_in"))
      (node (ref "U2") (pin "33") (pinfunction "POWERPAD_33") (pintype "bidirectional"))
      (node (ref "U2") (pin "5") (pinfunction "DGND_5") (pintype "power_in"))
      (node (ref "U4") (pin "11") (pinfunction "GND_11") (pintype "power_in"))
      (node (ref "U4") (pin "5") (pinfunction "ILIM_5") (pintype "passive"))
      (node (ref "U4") (pin "8") (pinfunction "GND_2_8") (pintype "power_in"))
    )
    (net (code "24") (name "Net-(C54-Pad2)") (class "Default")
      (node (ref "C54") (pin "2") (pinfunction "2_2") (pintype "passive"))
      (node (ref "R11") (pin "2") (pinfunction "2_2") (pintype "passive"))
    )
    (net (code "25") (name "Net-(C55-Pad2)") (class "Default")
      (node (ref "C55") (pin "2") (pinfunction "2_2") (pintype "passive"))
      (node (ref "R12") (pin "2") (pinfunction "2_2") (pintype "passive"))
    )
    (net (code "26") (name "Net-(C56-Pad2)") (class "Default")
      (node (ref "C56") (pin "2") (pinfunction "2_2") (pintype "passive"))
      (node (ref "R13") (pin "2") (pinfunction "2_2") (pintype "passive"))
    )
    (net (code "27") (name "Net-(C57-Pad2)") (class "Default")
      (node (ref "C57") (pin "2") (pinfunction "2_2") (pintype "passive"))
      (node (ref "R14") (pin "2") (pinfunction "2_2") (pintype "passive"))
    )
    (net (code "28") (name "Net-(C58-Pad2)") (class "Default")
      (node (ref "C58") (pin "2") (pinfunction "2_2") (pintype "passive"))
      (node (ref "R15") (pin "2") (pinfunction "2_2") (pintype "passive"))
    )
    (net (code "29") (name "Net-(C59-Pad2)") (class "Default")
      (node (ref "C59") (pin "2") (pinfunction "2_2") (pintype "passive"))
      (node (ref "R16") (pin "2") (pinfunction "2_2") (pintype "passive"))
    )
    (net (code "30") (name "Net-(C60-Pad2)") (class "Default")
      (node (ref "C60") (pin "2") (pinfunction "2_2") (pintype "passive"))
      (node (ref "R17") (pin "2") (pinfunction "2_2") (pintype "passive"))
    )
    (net (code "31") (name "Net-(C61-Pad2)") (class "Default")
      (node (ref "C61") (pin "2") (pinfunction "2_2") (pintype "passive"))
      (node (ref "R18") (pin "2") (pinfunction "2_2") (pintype "passive"))
    )
    (net (code "32") (name "Net-(C64-Pad1)") (class "Default")
      (node (ref "C64") (pin "1") (pinfunction "1_1") (pintype "passive"))
      (node (ref "C66") (pin "1") (pinfunction "1_1") (pintype "passive"))
      (node (ref "L9") (pin "2") (pinfunction "2_2") (pintype "passive"))
      (node (ref "R19") (pin "1") (pinfunction "1_1") (pintype "passive"))
    )
    (net (code "33") (name "Net-(C65-Pad1)") (class "Default")
      (node (ref "C65") (pin "1") (pinfunction "1_1") (pintype "passive"))
      (node (ref "C67") (pin "1") (pinfunction "1_1") (pintype "passive"))
      (node (ref "L10") (pin "2") (pinfunction "2_2") (pintype "passive"))
      (node (ref "R20") (pin "1") (pinfunction "1_1") (pintype "passive"))
    )
    (net (code "34") (name "Net-(C66-Pad2)") (class "Default")
      (node (ref "C66") (pin "2") (pinfunction "2_2") (pintype "passive"))
      (node (ref "R22") (pin "2") (pinfunction "2_2") (pintype "passive"))
    )
    (net (code "35") (name "Net-(C67-Pad2)") (class "Default")
      (node (ref "C67") (pin "2") (pinfunction "2_2") (pintype "passive"))
      (node (ref "R24") (pin "2") (pinfunction "2_2") (pintype "passive"))
    )
    (net (code "36") (name "Net-(C68-Pad2)") (class "Default")
      (node (ref "C68") (pin "2") (pinfunction "2_2") (pintype "passive"))
      (node (ref "R21") (pin "2") (pinfunction "2_2") (pintype "passive"))
    )
    (net (code "37") (name "Net-(C69-Pad2)") (class "Default")
      (node (ref "C69") (pin "2") (pinfunction "2_2") (pintype "passive"))
      (node (ref "R23") (pin "2") (pinfunction "2_2") (pintype "passive"))
    )
    (net (code "38") (name "Net-(C72-Pad2)") (class "Default")
      (node (ref "C72") (pin "2") (pinfunction "2_2") (pintype "passive"))
      (node (ref "J2") (pin "2") (pinfunction "2_2") (pintype "bidirectional"))
      (node (ref "L4") (pin "2") (pinfunction "2_2") (pintype "passive"))
      (node (ref "R14") (pin "1") (pinfunction "1_1") (pintype "passive"))
    )
    (net (code "39") (name "Net-(C73-Pad2)") (class "Default")
      (node (ref "C73") (pin "2") (pinfunction "2_2") (pintype "passive"))
      (node (ref "J2") (pin "1") (pinfunction "1_1") (pintype "bidirectional"))
      (node (ref "L3") (pin "2") (pinfunction "2_2") (pintype "passive"))
      (node (ref "R13") (pin "1") (pinfunction "1_1") (pintype "passive"))
    )
    (net (code "40") (name "Net-(C74-Pad2)") (class "Default")
      (node (ref "C74") (pin "2") (pinfunction "2_2") (pintype "passive"))
      (node (ref "J1") (pin "1") (pinfunction "1_1") (pintype "bidirectional"))
      (node (ref "L2") (pin "2") (pinfunction "2_2") (pintype "passive"))
      (node (ref "R12") (pin "1") (pinfunction "1_1") (pintype "passive"))
    )
    (net (code "41") (name "Net-(C75-Pad2)") (class "Default")
      (node (ref "C75") (pin "2") (pinfunction "2_2") (pintype "passive"))
      (node (ref "J1") (pin "2") (pinfunction "2_2") (pintype "bidirectional"))
      (node (ref "L1") (pin "2") (pinfunction "2_2") (pintype "passive"))
      (node (ref "R11") (pin "1") (pinfunction "1_1") (pintype "passive"))
    )
    (net (code "42") (name "Net-(C76-Pad2)") (class "Default")
      (node (ref "C76") (pin "2") (pinfunction "2_2") (pintype "passive"))
      (node (ref "J4") (pin "2") (pinfunction "2_2") (pintype "bidirectional"))
      (node (ref "L8") (pin "2") (pinfunction "2_2") (pintype "passive"))
      (node (ref "R18") (pin "1") (pinfunction "1_1") (pintype "passive"))
    )
    (net (code "43") (name "Net-(C77-Pad2)") (class "Default")
      (node (ref "C77") (pin "2") (pinfunction "2_2") (pintype "passive"))
      (node (ref "J4") (pin "1") (pinfunction "1_1") (pintype "bidirectional"))
      (node (ref "L7") (pin "2") (pinfunction "2_2") (pintype "passive"))
      (node (ref "R17") (pin "1") (pinfunction "1_1") (pintype "passive"))
    )
    (net (code "44") (name "Net-(C78-Pad2)") (class "Default")
      (node (ref "C78") (pin "2") (pinfunction "2_2") (pintype "passive"))
      (node (ref "J3") (pin "1") (pinfunction "1_1") (pintype "bidirectional"))
      (node (ref "L6") (pin "2") (pinfunction "2_2") (pintype "passive"))
      (node (ref "R16") (pin "1") (pinfunction "1_1") (pintype "passive"))
    )
    (net (code "45") (name "Net-(C79-Pad2)") (class "Default")
      (node (ref "C79") (pin "2") (pinfunction "2_2") (pintype "passive"))
      (node (ref "J3") (pin "2") (pinfunction "2_2") (pintype "bidirectional"))
      (node (ref "L5") (pin "2") (pinfunction "2_2") (pintype "passive"))
      (node (ref "R15") (pin "1") (pinfunction "1_1") (pintype "passive"))
    )
    (net (code "46") (name "Net-(MIC_L-2)") (class "Default")
      (node (ref "L9") (pin "1") (pinfunction "1_1") (pintype "passive"))
      (node (ref "MIC_L") (pin "1") (pinfunction "2_1") (pintype "passive"))
    )
    (net (code "47") (name "Net-(MIC_R-2)") (class "Default")
      (node (ref "L10") (pin "1") (pinfunction "1_1") (pintype "passive"))
      (node (ref "MIC_R") (pin "1") (pinfunction "2_1") (pintype "passive"))
    )
    (net (code "48") (name "Net-(Q1-G)") (class "Default")
      (node (ref "C71") (pin "2") (pinfunction "2_2") (pintype "passive"))
      (node (ref "Q1") (pin "2") (pinfunction "G_2") (pintype "passive"))
      (node (ref "R28") (pin "1") (pinfunction "1_1") (pintype "passive"))
    )
    (net (code "49") (name "Net-(TP1-1)") (class "Default")
      (node (ref "R3") (pin "1") (pinfunction "1_1") (pintype "passive"))
      (node (ref "TP1") (pin "P$1") (pinfunction "1_P$1") (pintype "bidirectional"))
      (node (ref "U1") (pin "10") (pinfunction "GPIO1_10") (pintype "bidirectional"))
    )
    (net (code "50") (name "Net-(TP3-1)") (class "Default")
      (node (ref "R4") (pin "1") (pinfunction "1_1") (pintype "passive"))
      (node (ref "TP3") (pin "P$1") (pinfunction "1_P$1") (pintype "bidirectional"))
      (node (ref "U1") (pin "9") (pinfunction "GPIOO_9") (pintype "bidirectional"))
    )
    (net (code "51") (name "Net-(TP4-1)") (class "Default")
      (node (ref "R6") (pin "1") (pinfunction "1_1") (pintype "passive"))
      (node (ref "TP4") (pin "P$1") (pinfunction "1_P$1") (pintype "bidirectional"))
      (node (ref "U2") (pin "10") (pinfunction "GPIO1_10") (pintype "bidirectional"))
    )
    (net (code "52") (name "Net-(TP5-1)") (class "Default")
      (node (ref "TP5") (pin "P$1") (pinfunction "1_P$1") (pintype "bidirectional"))
      (node (ref "U2") (pin "11") (pinfunction "GPIO2_11") (pintype "bidirectional"))
    )
    (net (code "53") (name "Net-(TP6-1)") (class "Default")
      (node (ref "R7") (pin "1") (pinfunction "1_1") (pintype "passive"))
      (node (ref "TP6") (pin "P$1") (pinfunction "1_P$1") (pintype "bidirectional"))
      (node (ref "U2") (pin "9") (pinfunction "GPIOO_9") (pintype "bidirectional"))
    )
    (net (code "54") (name "Net-(TP7-1)") (class "Default")
      (node (ref "C70") (pin "2") (pinfunction "2_2") (pintype "passive"))
      (node (ref "R26") (pin "2") (pinfunction "2_2") (pintype "passive"))
      (node (ref "TP7") (pin "P$1") (pinfunction "1_P$1") (pintype "bidirectional"))
      (node (ref "U$1") (pin "P$8") (pinfunction "RESET_P$8") (pintype "bidirectional"))
    )
    (net (code "55") (name "Net-(U1-AVDD)") (class "Default")
      (node (ref "C23") (pin "1") (pinfunction "1_1") (pintype "passive"))
      (node (ref "U1") (pin "19") (pinfunction "AVDD_19") (pintype "power_in"))
    )
    (net (code "56") (name "Net-(U1-BST_A+)") (class "Default")
      (node (ref "C27") (pin "1") (pinfunction "1_1") (pintype "passive"))
      (node (ref "U1") (pin "1") (pinfunction "BST_A+_1") (pintype "power_in"))
    )
    (net (code "57") (name "Net-(U1-BST_A-)") (class "Default")
      (node (ref "C28") (pin "1") (pinfunction "1_1") (pintype "passive"))
      (node (ref "U1") (pin "29") (pinfunction "BST_A-_29") (pintype "power_in"))
    )
    (net (code "58") (name "Net-(U1-BST_B+)") (class "Default")
      (node (ref "C29") (pin "1") (pinfunction "1_1") (pintype "passive"))
      (node (ref "U1") (pin "24") (pinfunction "BST_B+_24") (pintype "power_in"))
    )
    (net (code "59") (name "Net-(U1-BST_B-)") (class "Default")
      (node (ref "C30") (pin "1") (pinfunction "1_1") (pintype "passive"))
      (node (ref "U1") (pin "28") (pinfunction "BST_B-_28") (pintype "power_in"))
    )
    (net (code "60") (name "Net-(U1-GVDD)") (class "Default")
      (node (ref "C26") (pin "1") (pinfunction "1_1") (pintype "passive"))
      (node (ref "U1") (pin "18") (pinfunction "GVDD_18") (pintype "power_in"))
    )
    (net (code "61") (name "Net-(U1-OUT_A+)") (class "Default")
      (node (ref "C27") (pin "2") (pinfunction "2_2") (pintype "passive"))
      (node (ref "L1") (pin "1") (pinfunction "1_1") (pintype "passive"))
      (node (ref "U1") (pin "2") (pinfunction "OUT_A+_2") (pintype "output"))
    )
    (net (code "62") (name "Net-(U1-OUT_A-)") (class "Default")
      (node (ref "C28") (pin "2") (pinfunction "2_2") (pintype "passive"))
      (node (ref "L2") (pin "1") (pinfunction "1_1") (pintype "passive"))
      (node (ref "U1") (pin "30") (pinfunction "OUT_A-_30") (pintype "output"))
    )
    (net (code "63") (name "Net-(U1-OUT_B+)") (class "Default")
      (node (ref "C29") (pin "2") (pinfunction "2_2") (pintype "passive"))
      (node (ref "L3") (pin "1") (pinfunction "1_1") (pintype "passive"))
      (node (ref "U1") (pin "23") (pinfunction "OUT_B+_23") (pintype "output"))
    )
    (net (code "64") (name "Net-(U1-OUT_B-)") (class "Default")
      (node (ref "C30") (pin "2") (pinfunction "2_2") (pintype "passive"))
      (node (ref "L4") (pin "1") (pinfunction "1_1") (pintype "passive"))
      (node (ref "U1") (pin "27") (pinfunction "OUT_B-_27") (pintype "output"))
    )
    (net (code "65") (name "Net-(U1-VR_DIG)") (class "Default")
      (node (ref "C21") (pin "1") (pinfunction "1_1") (pintype "passive"))
      (node (ref "U1") (pin "7") (pinfunction "VR_DIG_7") (pintype "power_in"))
    )
    (net (code "66") (name "Net-(U2-ADR)") (class "Default")
      (node (ref "R1") (pin "2") (pinfunction "2_2") (pintype "passive"))
      (node (ref "U2") (pin "8") (pinfunction "ADR_8") (pintype "input"))
    )
    (net (code "67") (name "Net-(U2-AVDD)") (class "Default")
      (node (ref "C24") (pin "1") (pinfunction "1_1") (pintype "passive"))
      (node (ref "U2") (pin "19") (pinfunction "AVDD_19") (pintype "power_in"))
    )
    (net (code "68") (name "Net-(U2-BST_A+)") (class "Default")
      (node (ref "C31") (pin "1") (pinfunction "1_1") (pintype "passive"))
      (node (ref "U2") (pin "1") (pinfunction "BST_A+_1") (pintype "power_in"))
    )
    (net (code "69") (name "Net-(U2-BST_A-)") (class "Default")
      (node (ref "C32") (pin "1") (pinfunction "1_1") (pintype "passive"))
      (node (ref "U2") (pin "29") (pinfunction "BST_A-_29") (pintype "power_in"))
    )
    (net (code "70") (name "Net-(U2-BST_B+)") (class "Default")
      (node (ref "C33") (pin "1") (pinfunction "1_1") (pintype "passive"))
      (node (ref "U2") (pin "24") (pinfunction "BST_B+_24") (pintype "power_in"))
    )
    (net (code "71") (name "Net-(U2-BST_B-)") (class "Default")
      (node (ref "C34") (pin "1") (pinfunction "1_1") (pintype "passive"))
      (node (ref "U2") (pin "28") (pinfunction "BST_B-_28") (pintype "power_in"))
    )
    (net (code "72") (name "Net-(U2-GVDD)") (class "Default")
      (node (ref "C25") (pin "1") (pinfunction "1_1") (pintype "passive"))
      (node (ref "U2") (pin "18") (pinfunction "GVDD_18") (pintype "power_in"))
    )
    (net (code "73") (name "Net-(U2-OUT_A+)") (class "Default")
      (node (ref "C31") (pin "2") (pinfunction "2_2") (pintype "passive"))
      (node (ref "L5") (pin "1") (pinfunction "1_1") (pintype "passive"))
      (node (ref "U2") (pin "2") (pinfunction "OUT_A+_2") (pintype "output"))
    )
    (net (code "74") (name "Net-(U2-OUT_A-)") (class "Default")
      (node (ref "C32") (pin "2") (pinfunction "2_2") (pintype "passive"))
      (node (ref "L6") (pin "1") (pinfunction "1_1") (pintype "passive"))
      (node (ref "U2") (pin "30") (pinfunction "OUT_A-_30") (pintype "output"))
    )
    (net (code "75") (name "Net-(U2-OUT_B+)") (class "Default")
      (node (ref "C33") (pin "2") (pinfunction "2_2") (pintype "passive"))
      (node (ref "L7") (pin "1") (pinfunction "1_1") (pintype "passive"))
      (node (ref "U2") (pin "23") (pinfunction "OUT_B+_23") (pintype "output"))
    )
    (net (code "76") (name "Net-(U2-OUT_B-)") (class "Default")
      (node (ref "C34") (pin "2") (pinfunction "2_2") (pintype "passive"))
      (node (ref "L8") (pin "1") (pinfunction "1_1") (pintype "passive"))
      (node (ref "U2") (pin "27") (pinfunction "OUT_B-_27") (pintype "output"))
    )
    (net (code "77") (name "Net-(U2-VR_DIG)") (class "Default")
      (node (ref "C22") (pin "1") (pinfunction "1_1") (pintype "passive"))
      (node (ref "U2") (pin "7") (pinfunction "VR_DIG_7") (pintype "power_in"))
    )
    (net (code "78") (name "Net-(U4-SET)") (class "Default")
      (node (ref "C43") (pin "1") (pinfunction "1_1") (pintype "passive"))
      (node (ref "R2") (pin "1") (pinfunction "1_1") (pintype "passive"))
      (node (ref "U4") (pin "7") (pinfunction "SET_7") (pintype "input"))
    )
    (net (code "79") (name "VBAT") (class "Default")
      (node (ref "C1") (pin "1") (pinfunction "1_1") (pintype "passive"))
      (node (ref "C10") (pin "1") (pinfunction "1_1") (pintype "passive"))
      (node (ref "C11") (pin "1") (pinfunction "1_1") (pintype "passive"))
      (node (ref "C12") (pin "1") (pinfunction "1_1") (pintype "passive"))
      (node (ref "C13") (pin "1") (pinfunction "1_1") (pintype "passive"))
      (node (ref "C14") (pin "1") (pinfunction "1_1") (pintype "passive"))
      (node (ref "C15") (pin "1") (pinfunction "1_1") (pintype "passive"))
      (node (ref "C16") (pin "1") (pinfunction "1_1") (pintype "passive"))
      (node (ref "C2") (pin "1") (pinfunction "1_1") (pintype "passive"))
      (node (ref "C3") (pin "1") (pinfunction "1_1") (pintype "passive"))
      (node (ref "C35") (pin "2") (pinfunction "2_2") (pintype "passive"))
      (node (ref "C36") (pin "1") (pinfunction "1_1") (pintype "passive"))
      (node (ref "C37") (pin "1") (pinfunction "1_1") (pintype "passive"))
      (node (ref "C38") (pin "1") (pinfunction "1_1") (pintype "passive"))
      (node (ref "C39") (pin "1") (pinfunction "1_1") (pintype "passive"))
      (node (ref "C4") (pin "1") (pinfunction "1_1") (pintype "passive"))
      (node (ref "C40") (pin "1") (pinfunction "1_1") (pintype "passive"))
      (node (ref "C41") (pin "1") (pinfunction "1_1") (pintype "passive"))
      (node (ref "C42") (pin "1") (pinfunction "1_1") (pintype "passive"))
      (node (ref "C45") (pin "1") (pinfunction "1_1") (pintype "passive"))
      (node (ref "C46") (pin "1") (pinfunction "1_1") (pintype "passive"))
      (node (ref "C47") (pin "1") (pinfunction "1_1") (pintype "passive"))
      (node (ref "C48") (pin "1") (pinfunction "1_1") (pintype "passive"))
      (node (ref "C49") (pin "1") (pinfunction "1_1") (pintype "passive"))
      (node (ref "C5") (pin "1") (pinfunction "1_1") (pintype "passive"))
      (node (ref "C50") (pin "1") (pinfunction "1_1") (pintype "passive"))
      (node (ref "C51") (pin "1") (pinfunction "1_1") (pintype "passive"))
      (node (ref "C52") (pin "1") (pinfunction "1_1") (pintype "passive"))
      (node (ref "C6") (pin "1") (pinfunction "1_1") (pintype "passive"))
      (node (ref "C7") (pin "1") (pinfunction "1_1") (pintype "passive"))
      (node (ref "C8") (pin "1") (pinfunction "1_1") (pintype "passive"))
      (node (ref "C80") (pin "1") (pinfunction "1_1") (pintype "passive"))
      (node (ref "C9") (pin "1") (pinfunction "1_1") (pintype "passive"))
      (node (ref "JP4") (pin "1") (pinfunction "1_1") (pintype "passive"))
      (node (ref "JP4") (pin "2") (pinfunction "2_2") (pintype "passive"))
      (node (ref "JP4") (pin "3") (pinfunction "3_3") (pintype "passive"))
      (node (ref "JP4") (pin "4") (pinfunction "4_4") (pintype "passive"))
      (node (ref "JP6") (pin "4") (pinfunction "4_4") (pintype "passive"))
      (node (ref "U1") (pin "21") (pinfunction "PVDD-3_21") (pintype "power_in"))
      (node (ref "U1") (pin "22") (pinfunction "PVDD-2_22") (pintype "power_in"))
      (node (ref "U1") (pin "3") (pinfunction "PVDD-1_3") (pintype "power_in"))
      (node (ref "U1") (pin "4") (pinfunction "PVDD_4") (pintype "power_in"))
      (node (ref "U2") (pin "21") (pinfunction "PVDD-3_21") (pintype "power_in"))
      (node (ref "U2") (pin "22") (pinfunction "PVDD-2_22") (pintype "power_in"))
      (node (ref "U2") (pin "3") (pinfunction "PVDD-1_3") (pintype "power_in"))
      (node (ref "U2") (pin "4") (pinfunction "PVDD_4") (pintype "power_in"))
      (node (ref "U4") (pin "1") (pinfunction "IN_2_1") (pintype "input"))
      (node (ref "U4") (pin "2") (pinfunction "IN_2") (pintype "input"))
      (node (ref "U4") (pin "6") (pinfunction "PGFB_6") (pintype "power_in"))
    )
    (net (code "80") (name "unconnected-(U$1-1.8V_OUT-PadP$35)") (class "Default")
      (node (ref "U$1") (pin "P$35") (pinfunction "1.8V_OUT_P$35") (pintype "bidirectional"))
    )
    (net (code "81") (name "unconnected-(U$1-AIO0-PadP$2)") (class "Default")
      (node (ref "U$1") (pin "P$2") (pinfunction "AIO0_P$2") (pintype "bidirectional"))
    )
    (net (code "82") (name "unconnected-(U$1-AIO1-PadP$3)") (class "Default")
      (node (ref "U$1") (pin "P$3") (pinfunction "AIO1_P$3") (pintype "bidirectional"))
    )
    (net (code "83") (name "unconnected-(U$1-BT_CTS-PadP$15)") (class "Default")
      (node (ref "U$1") (pin "P$15") (pinfunction "BT_CTS_P$15") (pintype "bidirectional"))
    )
    (net (code "84") (name "unconnected-(U$1-BT_RTS-PadP$16)") (class "Default")
      (node (ref "U$1") (pin "P$16") (pinfunction "BT_RTS_P$16") (pintype "bidirectional"))
    )
    (net (code "85") (name "unconnected-(U$1-EXT_ANT-PadP$51)") (class "Default")
      (node (ref "U$1") (pin "P$51") (pinfunction "EXT_ANT_P$51") (pintype "bidirectional"))
    )
    (net (code "86") (name "unconnected-(U$1-I2S_IN-PadP$5)") (class "Default")
      (node (ref "U$1") (pin "P$5") (pinfunction "I2S_IN_P$5") (pintype "bidirectional"))
    )
    (net (code "87") (name "unconnected-(U$1-LED1-PadP$18)") (class "Default")
      (node (ref "U$1") (pin "P$18") (pinfunction "LED1_P$18") (pintype "bidirectional"))
    )
    (net (code "88") (name "unconnected-(U$1-LED2-PadP$19)") (class "Default")
      (node (ref "U$1") (pin "P$19") (pinfunction "LED2_P$19") (pintype "bidirectional"))
    )
    (net (code "89") (name "unconnected-(U$1-PIO0-PadP$20)") (class "Default")
      (node (ref "U$1") (pin "P$20") (pinfunction "PIO0_P$20") (pintype "bidirectional"))
    )
    (net (code "90") (name "unconnected-(U$1-PIO1-PadP$21)") (class "Default")
      (node (ref "U$1") (pin "P$21") (pinfunction "PIO1_P$21") (pintype "bidirectional"))
    )
    (net (code "91") (name "unconnected-(U$1-PIO2-PadP$23)") (class "Default")
      (node (ref "U$1") (pin "P$23") (pinfunction "PIO2_P$23") (pintype "bidirectional"))
    )
    (net (code "92") (name "unconnected-(U$1-PIO3-PadP$24)") (class "Default")
      (node (ref "U$1") (pin "P$24") (pinfunction "PIO3_P$24") (pintype "bidirectional"))
    )
    (net (code "93") (name "unconnected-(U$1-PIO4-PadP$25)") (class "Default")
      (node (ref "U$1") (pin "P$25") (pinfunction "PIO4_P$25") (pintype "bidirectional"))
    )
    (net (code "94") (name "unconnected-(U$1-PIO5-PadP$26)") (class "Default")
      (node (ref "U$1") (pin "P$26") (pinfunction "PIO5_P$26") (pintype "bidirectional"))
    )
    (net (code "95") (name "unconnected-(U$1-PIO14-PadP$29)") (class "Default")
      (node (ref "U$1") (pin "P$29") (pinfunction "PIO14_P$29") (pintype "bidirectional"))
    )
    (net (code "96") (name "unconnected-(U$1-PIO15-PadP$30)") (class "Default")
      (node (ref "U$1") (pin "P$30") (pinfunction "PIO15_P$30") (pintype "bidirectional"))
    )
    (net (code "97") (name "unconnected-(U$1-SPI_CLK-PadP$12)") (class "Default")
      (node (ref "U$1") (pin "P$12") (pinfunction "SPI_CLK_P$12") (pintype "bidirectional"))
    )
    (net (code "98") (name "unconnected-(U$1-SPI_CSB-PadP$9)") (class "Default")
      (node (ref "U$1") (pin "P$9") (pinfunction "SPI_CSB_P$9") (pintype "bidirectional"))
    )
    (net (code "99") (name "unconnected-(U$1-SPI_MISO-PadP$11)") (class "Default")
      (node (ref "U$1") (pin "P$11") (pinfunction "SPI_MISO_P$11") (pintype "bidirectional"))
    )
    (net (code "100") (name "unconnected-(U$1-SPI_MOSI-PadP$10)") (class "Default")
      (node (ref "U$1") (pin "P$10") (pinfunction "SPI_MOSI_P$10") (pintype "bidirectional"))
    )
    (net (code "101") (name "unconnected-(U$1-SPK_LN-PadP$48)") (class "Default")
      (node (ref "U$1") (pin "P$48") (pinfunction "SPK_LN_P$48") (pintype "bidirectional"))
    )
    (net (code "102") (name "unconnected-(U$1-SPK_LP-PadP$49)") (class "Default")
      (node (ref "U$1") (pin "P$49") (pinfunction "SPK_LP_P$49") (pintype "bidirectional"))
    )
    (net (code "103") (name "unconnected-(U$1-SPK_RN-PadP$46)") (class "Default")
      (node (ref "U$1") (pin "P$46") (pinfunction "SPK_RN_P$46") (pintype "bidirectional"))
    )
    (net (code "104") (name "unconnected-(U$1-SPK_RP-PadP$47)") (class "Default")
      (node (ref "U$1") (pin "P$47") (pinfunction "SPK_RP_P$47") (pintype "bidirectional"))
    )
    (net (code "105") (name "unconnected-(U$1-USB_DN-PadP$38)") (class "Default")
      (node (ref "U$1") (pin "P$38") (pinfunction "USB_DN_P$38") (pintype "bidirectional"))
    )
    (net (code "106") (name "unconnected-(U$1-USB_DP-PadP$37)") (class "Default")
      (node (ref "U$1") (pin "P$37") (pinfunction "USB_DP_P$37") (pintype "bidirectional"))
    )
    (net (code "107") (name "unconnected-(U$1-VCC_CHG-PadP$39)") (class "Default")
      (node (ref "U$1") (pin "P$39") (pinfunction "VCC_CHG_P$39") (pintype "bidirectional"))
    )
    (net (code "108") (name "unconnected-(U$1-VDD_USB{slash}3.3VO-PadP$31)") (class "Default")
      (node (ref "U$1") (pin "P$31") (pinfunction "VDD_USB/3.3VO_P$31") (pintype "bidirectional"))
    )
  )
)
